# -modifi.net
KiCad netlist of a schematic drawn in Altium Designer
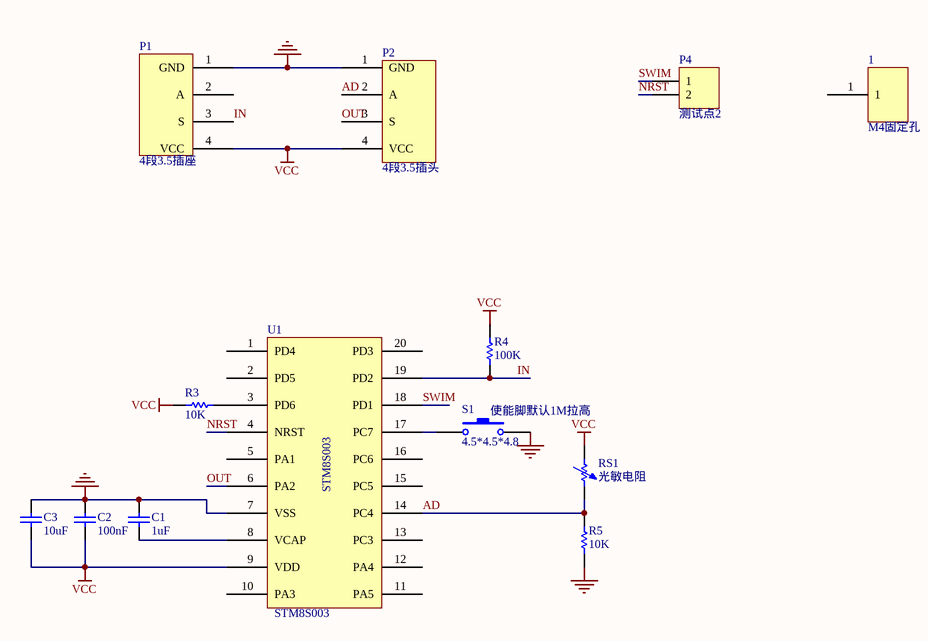
[diagram p0: 光敏开关-modifi.SchDoc]

(export (version "E")
  (design (tool "Eeschema 10.0.6"))
  (components
    (comp (ref "1") (value "M4固定孔") (footprint "M4固定孔") (libsource (lib "DDL6.30") (part "M4固定孔")))
    (comp (ref "C1")
      (value "1uF")
      (footprint "0603C")
      (description "Capacitor")
      (fields (field (name "PUBLISHER") "Altium Limited"))
      (libsource (lib "Miscellaneous Devices") (part "Cap"))
    )
    (comp (ref "C2")
      (value "100nF")
      (footprint "0603C")
      (description "Capacitor")
      (fields (field (name "PUBLISHER") "Altium Limited"))
      (libsource (lib "Miscellaneous Devices") (part "Cap"))
    )
    (comp (ref "C3")
      (value "10uF")
      (footprint "0603C")
      (description "Capacitor")
      (fields (field (name "PUBLISHER") "Altium Limited"))
      (libsource (lib "Miscellaneous Devices") (part "Cap"))
    )
    (comp (ref "P1") (value "4段3.5插座") (footprint "4段3.5耳机贴片座") (libsource (lib "DDL6.30") (part "4段3.5插座")))
    (comp (ref "P2") (value "4段3.5插头") (footprint "4段3.5插头") (libsource (lib "DDL6.30") (part "4段3.5插头")))
    (comp (ref "P4")
      (value "测试点2")
      (footprint "2SMT-2.54")
      (description "Header, 2-Pin")
      (fields (field (name "PUBLISHER") "Altium Limited"))
      (libsource (lib "Miscellaneous Connectors") (part "Header 2"))
    )
    (comp (ref "R3")
      (value "10K")
      (footprint "0603R")
      (description "Resistor")
      (fields (field (name "PUBLISHER") "Altium Limited"))
      (libsource (lib "Miscellaneous Devices") (part "Res1"))
    )
    (comp (ref "R4")
      (value "100K")
      (footprint "0603R")
      (description "Resistor")
      (fields (field (name "PUBLISHER") "Altium Limited"))
      (libsource (lib "Miscellaneous Devices") (part "Res1"))
    )
    (comp (ref "R5")
      (value "10K")
      (footprint "0603R")
      (description "Resistor")
      (fields (field (name "PUBLISHER") "Altium Limited"))
      (libsource (lib "Miscellaneous Devices") (part "Res1"))
    )
    (comp (ref "RS1")
      (value "光敏电阻")
      (footprint "光敏电阻")
      (description "Variable Resistor")
      (fields (field (name "PUBLISHER") "Altium Limited"))
      (libsource (lib "Miscellaneous Devices") (part "Res Adj1"))
    )
    (comp (ref "S1")
      (value "4.5*4.5*4.8")
      (footprint "按键4.5*4.5*4.8")
      (description "Switch")
      (fields (field (name "PUBLISHER") "Altium Limited"))
      (libsource (lib "Miscellaneous Devices") (part "SW-PB"))
    )
    (comp (ref "U1") (value "STM8S003") (footprint "TSSOP20") (libsource (lib "DDL6.30") (part "STM8S003")))
  )
  (nets
    (net (code "1") (name "/AD") (class "Default")
      (node (ref "P2") (pin "2") (pinfunction "A_2") (pintype "passive"))
      (node (ref "R5") (pin "2") (pinfunction "2_2") (pintype "passive"))
      (node (ref "RS1") (pin "2") (pinfunction "2_2") (pintype "passive"))
      (node (ref "U1") (pin "14") (pinfunction "PC4_14") (pintype "passive"))
    )
    (net (code "2") (name "/IN") (class "Default")
      (node (ref "P1") (pin "3") (pinfunction "S_3") (pintype "passive"))
      (node (ref "R4") (pin "2") (pinfunction "2_2") (pintype "passive"))
      (node (ref "U1") (pin "19") (pinfunction "PD2_19") (pintype "passive"))
    )
    (net (code "3") (name "/NRST") (class "Default")
      (node (ref "P4") (pin "2") (pinfunction "2_2") (pintype "passive"))
      (node (ref "U1") (pin "4") (pinfunction "NRST_4") (pintype "passive"))
    )
    (net (code "4") (name "/OUT") (class "Default")
      (node (ref "P2") (pin "3") (pinfunction "S_3") (pintype "passive"))
      (node (ref "U1") (pin "6") (pinfunction "PA2_6") (pintype "passive"))
    )
    (net (code "5") (name "/SWIM") (class "Default")
      (node (ref "P4") (pin "1") (pinfunction "1_1") (pintype "passive"))
      (node (ref "U1") (pin "18") (pinfunction "PD1_18") (pintype "passive"))
    )
    (net (code "6") (name "GND") (class "Default")
      (node (ref "C1") (pin "2") (pinfunction "2_2") (pintype "passive"))
      (node (ref "C2") (pin "2") (pinfunction "2_2") (pintype "passive"))
      (node (ref "C3") (pin "2") (pinfunction "2_2") (pintype "passive"))
      (node (ref "P1") (pin "1") (pinfunction "GND_1") (pintype "passive"))
      (node (ref "P2") (pin "1") (pinfunction "GND_1") (pintype "passive"))
      (node (ref "R5") (pin "1") (pinfunction "1_1") (pintype "passive"))
      (node (ref "S1") (pin "2") (pinfunction "2_2") (pintype "passive"))
      (node (ref "U1") (pin "7") (pinfunction "VSS_7") (pintype "passive"))
    )
    (net (code "7") (name "Net-(U1-PC7)") (class "Default")
      (node (ref "S1") (pin "1") (pinfunction "1_1") (pintype "passive"))
      (node (ref "U1") (pin "17") (pinfunction "PC7_17") (pintype "passive"))
    )
    (net (code "8") (name "Net-(U1-PD6)") (class "Default")
      (node (ref "R3") (pin "1") (pinfunction "1_1") (pintype "passive"))
      (node (ref "U1") (pin "3") (pinfunction "PD6_3") (pintype "passive"))
    )
    (net (code "9") (name "Net-(U1-VCAP)") (class "Default")
      (node (ref "C1") (pin "1") (pinfunction "1_1") (pintype "passive"))
      (node (ref "U1") (pin "8") (pinfunction "VCAP_8") (pintype "passive"))
    )
    (net (code "10") (name "VCC") (class "Default")
      (node (ref "C2") (pin "1") (pinfunction "1_1") (pintype "passive"))
      (node (ref "C3") (pin "1") (pinfunction "1_1") (pintype "passive"))
      (node (ref "P1") (pin "4") (pinfunction "VCC_4") (pintype "passive"))
      (node (ref "P2") (pin "4") (pinfunction "VCC_4") (pintype "passive"))
      (node (ref "R3") (pin "2") (pinfunction "2_2") (pintype "passive"))
      (node (ref "R4") (pin "1") (pinfunction "1_1") (pintype "passive"))
      (node (ref "RS1") (pin "1") (pinfunction "1_1") (pintype "passive"))
      (node (ref "U1") (pin "9") (pinfunction "VDD_9") (pintype "passive"))
    )
    (net (code "11") (name "unconnected-(1-Pad1)") (class "Default")
      (node (ref "1") (pin "1") (pinfunction "1_1") (pintype "passive"))
    )
    (net (code "12") (name "unconnected-(P1-A-Pad2)") (class "Default")
      (node (ref "P1") (pin "2") (pinfunction "A_2") (pintype "passive"))
    )
    (net (code "13") (name "unconnected-(U1-PA1-Pad5)") (class "Default")
      (node (ref "U1") (pin "5") (pinfunction "PA1_5") (pintype "passive"))
    )
    (net (code "14") (name "unconnected-(U1-PA3-Pad10)") (class "Default")
      (node (ref "U1") (pin "10") (pinfunction "PA3_10") (pintype "passive"))
    )
    (net (code "15") (name "unconnected-(U1-PA4-Pad12)") (class "Default")
      (node (ref "U1") (pin "12") (pinfunction "PA4_12") (pintype "passive"))
    )
    (net (code "16") (name "unconnected-(U1-PA5-Pad11)") (class "Default")
      (node (ref "U1") (pin "11") (pinfunction "PA5_11") (pintype "passive"))
    )
    (net (code "17") (name "unconnected-(U1-PC3-Pad13)") (class "Default")
      (node (ref "U1") (pin "13") (pinfunction "PC3_13") (pintype "passive"))
    )
    (net (code "18") (name "unconnected-(U1-PC5-Pad15)") (class "Default")
      (node (ref "U1") (pin "15") (pinfunction "PC5_15") (pintype "passive"))
    )
    (net (code "19") (name "unconnected-(U1-PC6-Pad16)") (class "Default")
      (node (ref "U1") (pin "16") (pinfunction "PC6_16") (pintype "passive"))
    )
    (net (code "20") (name "unconnected-(U1-PD3-Pad20)") (class "Default")
      (node (ref "U1") (pin "20") (pinfunction "PD3_20") (pintype "passive"))
    )
    (net (code "21") (name "unconnected-(U1-PD4-Pad1)") (class "Default")
      (node (ref "U1") (pin "1") (pinfunction "PD4_1") (pintype "passive"))
    )
    (net (code "22") (name "unconnected-(U1-PD5-Pad2)") (class "Default")
      (node (ref "U1") (pin "2") (pinfunction "PD5_2") (pintype "passive"))
    )
  )
)
